# Simple-LM324-OP-AMP-based-USB-Li-ion-cha.net
KiCad netlist of a schematic drawn in EAGLE
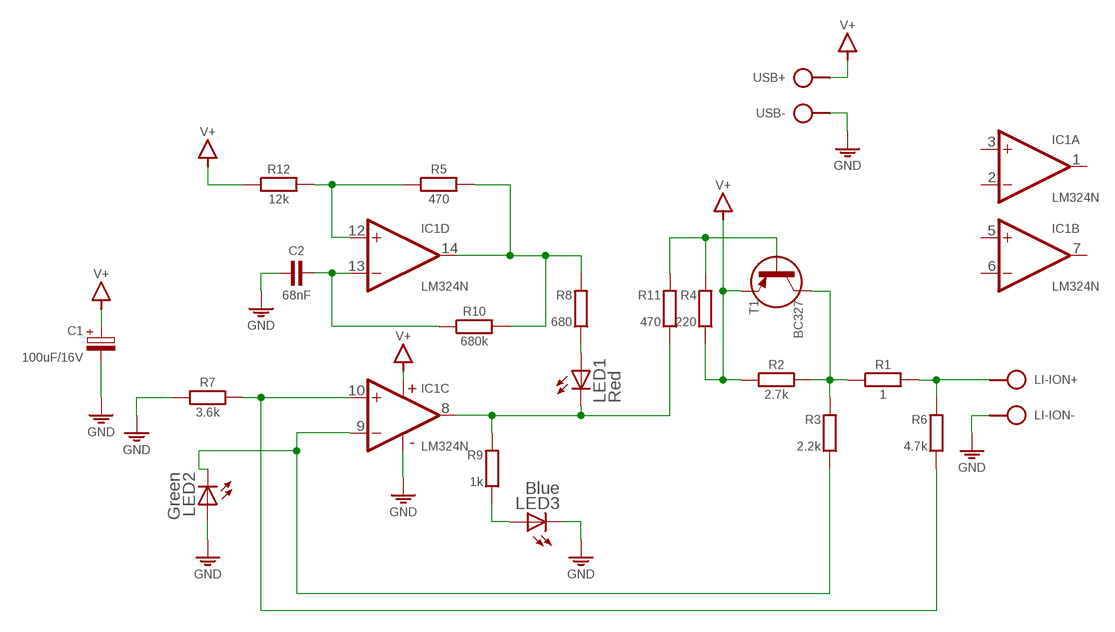
[diagram p0: schematic, sheet 1]

(export (version "E")
  (design (tool "Eeschema 10.0.6"))
  (components
    (comp (ref "C1")
      (value "100uF/16V")
      (footprint "eagle-import:E2,5-5")
      (libsource (lib "eagle-import") (part "CPOLE2.5-5"))
    )
    (comp (ref "C2")
      (value "68nF")
      (footprint "eagle-import:C050-020X044")
      (libsource (lib "eagle-import") (part "C-H050-020X044"))
    )
    (comp (ref "IC1")
      (value "LM324N")
      (footprint "eagle-import:DIL14")
      (libsource (lib "eagle-import") (part "LM324N"))
    )
    (comp (ref "LED1")
      (value "Red")
      (footprint "eagle-import:LED3MM")
      (libsource (lib "eagle-import") (part "LED3MM"))
    )
    (comp (ref "LED2")
      (value "Green")
      (footprint "eagle-import:LED3MM")
      (libsource (lib "eagle-import") (part "LED3MM"))
    )
    (comp (ref "LED3")
      (value "Blue")
      (footprint "eagle-import:LED3MM")
      (libsource (lib "eagle-import") (part "LED3MM"))
    )
    (comp (ref "LI-ION")
      (value "SPAD+-+-")
      (footprint "eagle-import:SPAD+-")
      (libsource (lib "eagle-import") (part "SPAD+-+-"))
    )
    (comp (ref "R1")
      (value "1")
      (footprint "eagle-import:0204_10")
      (libsource (lib "eagle-import") (part "R-H0204/10"))
    )
    (comp (ref "R2")
      (value "2.7k")
      (footprint "eagle-import:0204_10-V")
      (libsource (lib "eagle-import") (part "R-H0204/10-V"))
    )
    (comp (ref "R3")
      (value "2.2k")
      (footprint "eagle-import:0204_10-V")
      (libsource (lib "eagle-import") (part "R0204/10-V"))
    )
    (comp (ref "R4")
      (value "220")
      (footprint "eagle-import:0204_10-V")
      (libsource (lib "eagle-import") (part "R0204/10-V"))
    )
    (comp (ref "R5")
      (value "470")
      (footprint "eagle-import:0204_10")
      (libsource (lib "eagle-import") (part "R-H0204/10"))
    )
    (comp (ref "R6")
      (value "4.7k")
      (footprint "eagle-import:0204_10-V")
      (libsource (lib "eagle-import") (part "R0204/10-V"))
    )
    (comp (ref "R7")
      (value "3.6k")
      (footprint "eagle-import:0204_10")
      (libsource (lib "eagle-import") (part "R-H0204/10"))
    )
    (comp (ref "R8")
      (value "680")
      (footprint "eagle-import:0204_10-V")
      (libsource (lib "eagle-import") (part "R0204/10-V"))
    )
    (comp (ref "R9")
      (value "1k")
      (footprint "eagle-import:0204_7-V")
      (libsource (lib "eagle-import") (part "R0204/7-V"))
    )
    (comp (ref "R10")
      (value "680k")
      (footprint "eagle-import:0204_10")
      (libsource (lib "eagle-import") (part "R-H0204/10"))
    )
    (comp (ref "R11")
      (value "470")
      (footprint "eagle-import:0204_10-V")
      (libsource (lib "eagle-import") (part "R0204/10-V"))
    )
    (comp (ref "R12")
      (value "12k")
      (footprint "eagle-import:0204_10-V")
      (libsource (lib "eagle-import") (part "R-H0204/10-V"))
    )
    (comp (ref "T1")
      (value "BC327")
      (footprint "eagle-import:TO92")
      (libsource (lib "eagle-import") (part "BC327"))
    )
    (comp (ref "USB")
      (value "SPAD+--+")
      (footprint "eagle-import:SPAD-+")
      (libsource (lib "eagle-import") (part "SPAD+--+"))
    )
  )
  (nets
    (net (code "1") (name "GND") (class "Default")
      (node (ref "C1") (pin "-") (pinfunction "-_-") (pintype "passive"))
      (node (ref "C2") (pin "1") (pinfunction "1_1") (pintype "passive"))
      (node (ref "IC1") (pin "11") (pinfunction "V-_11") (pintype "power_in"))
      (node (ref "LED2") (pin "A") (pinfunction "A_A") (pintype "passive"))
      (node (ref "LED3") (pin "K") (pinfunction "C_K") (pintype "passive"))
      (node (ref "LI-ION") (pin "1") (pinfunction "P$1_1") (pintype "passive"))
      (node (ref "R7") (pin "1") (pinfunction "1_1") (pintype "passive"))
      (node (ref "USB") (pin "1") (pinfunction "P$1_1") (pintype "passive"))
    )
    (net (code "2") (name "Net-(IC1C-+IN)") (class "Default")
      (node (ref "IC1") (pin "10") (pinfunction "+IN_10") (pintype "input"))
      (node (ref "R6") (pin "2") (pinfunction "2_2") (pintype "passive"))
      (node (ref "R7") (pin "2") (pinfunction "2_2") (pintype "passive"))
    )
    (net (code "3") (name "Net-(IC1C--IN)") (class "Default")
      (node (ref "IC1") (pin "9") (pinfunction "-IN_9") (pintype "input"))
      (node (ref "LED2") (pin "K") (pinfunction "C_K") (pintype "passive"))
      (node (ref "R3") (pin "2") (pinfunction "2_2") (pintype "passive"))
    )
    (net (code "4") (name "Net-(IC1C-OUT)") (class "Default")
      (node (ref "IC1") (pin "8") (pinfunction "OUT_8") (pintype "output"))
      (node (ref "LED1") (pin "K") (pinfunction "C_K") (pintype "passive"))
      (node (ref "R11") (pin "2") (pinfunction "2_2") (pintype "passive"))
      (node (ref "R9") (pin "2") (pinfunction "1_2") (pintype "passive"))
    )
    (net (code "5") (name "Net-(IC1D-+IN)") (class "Default")
      (node (ref "IC1") (pin "12") (pinfunction "+IN_12") (pintype "input"))
      (node (ref "R12") (pin "2") (pinfunction "2_2") (pintype "passive"))
      (node (ref "R5") (pin "1") (pinfunction "1_1") (pintype "passive"))
    )
    (net (code "6") (name "Net-(IC1D--IN)") (class "Default")
      (node (ref "C2") (pin "2") (pinfunction "2_2") (pintype "passive"))
      (node (ref "IC1") (pin "13") (pinfunction "-IN_13") (pintype "input"))
      (node (ref "R10") (pin "1") (pinfunction "1_1") (pintype "passive"))
    )
    (net (code "7") (name "Net-(IC1D-OUT)") (class "Default")
      (node (ref "IC1") (pin "14") (pinfunction "OUT_14") (pintype "output"))
      (node (ref "R10") (pin "2") (pinfunction "2_2") (pintype "passive"))
      (node (ref "R5") (pin "2") (pinfunction "2_2") (pintype "passive"))
      (node (ref "R8") (pin "1") (pinfunction "1_1") (pintype "passive"))
    )
    (net (code "8") (name "Net-(LED1-PadA)") (class "Default")
      (node (ref "LED1") (pin "A") (pinfunction "A_A") (pintype "passive"))
      (node (ref "R8") (pin "2") (pinfunction "2_2") (pintype "passive"))
    )
    (net (code "9") (name "Net-(LI-IONA-P$1)") (class "Default")
      (node (ref "LI-ION") (pin "2") (pinfunction "P$1_2") (pintype "passive"))
      (node (ref "R1") (pin "2") (pinfunction "2_2") (pintype "passive"))
      (node (ref "R6") (pin "1") (pinfunction "1_1") (pintype "passive"))
    )
    (net (code "10") (name "Net-(R9-2)") (class "Default")
      (node (ref "LED3") (pin "A") (pinfunction "A_A") (pintype "passive"))
      (node (ref "R9") (pin "1") (pinfunction "2_1") (pintype "passive"))
    )
    (net (code "11") (name "Net-(T1-B)") (class "Default")
      (node (ref "R11") (pin "1") (pinfunction "1_1") (pintype "passive"))
      (node (ref "R4") (pin "1") (pinfunction "1_1") (pintype "passive"))
      (node (ref "T1") (pin "2") (pinfunction "B_2") (pintype "passive"))
    )
    (net (code "12") (name "Net-(T1-C)") (class "Default")
      (node (ref "R1") (pin "1") (pinfunction "1_1") (pintype "passive"))
      (node (ref "R2") (pin "2") (pinfunction "2_2") (pintype "passive"))
      (node (ref "R3") (pin "1") (pinfunction "1_1") (pintype "passive"))
      (node (ref "T1") (pin "1") (pinfunction "C_1") (pintype "passive"))
    )
    (net (code "13") (name "V+") (class "Default")
      (node (ref "C1") (pin "+") (pinfunction "+_+") (pintype "passive"))
      (node (ref "IC1") (pin "4") (pinfunction "V+_4") (pintype "power_in"))
      (node (ref "R12") (pin "1") (pinfunction "1_1") (pintype "passive"))
      (node (ref "R2") (pin "1") (pinfunction "1_1") (pintype "passive"))
      (node (ref "R4") (pin "2") (pinfunction "2_2") (pintype "passive"))
      (node (ref "T1") (pin "3") (pinfunction "E_3") (pintype "passive"))
      (node (ref "USB") (pin "2") (pinfunction "P$1_2") (pintype "passive"))
    )
    (net (code "14") (name "unconnected-(IC1A-+IN-Pad3)") (class "Default")
      (node (ref "IC1") (pin "3") (pinfunction "+IN_3") (pintype "input"))
    )
    (net (code "15") (name "unconnected-(IC1A--IN-Pad2)") (class "Default")
      (node (ref "IC1") (pin "2") (pinfunction "-IN_2") (pintype "input"))
    )
    (net (code "16") (name "unconnected-(IC1A-OUT-Pad1)") (class "Default")
      (node (ref "IC1") (pin "1") (pinfunction "OUT_1") (pintype "output"))
    )
    (net (code "17") (name "unconnected-(IC1B-+IN-Pad5)") (class "Default")
      (node (ref "IC1") (pin "5") (pinfunction "+IN_5") (pintype "input"))
    )
    (net (code "18") (name "unconnected-(IC1B--IN-Pad6)") (class "Default")
      (node (ref "IC1") (pin "6") (pinfunction "-IN_6") (pintype "input"))
    )
    (net (code "19") (name "unconnected-(IC1B-OUT-Pad7)") (class "Default")
      (node (ref "IC1") (pin "7") (pinfunction "OUT_7") (pintype "output"))
    )
  )
)
